# laser_show_peripheral.net
KiCad netlist of a schematic drawn in Altium Designer
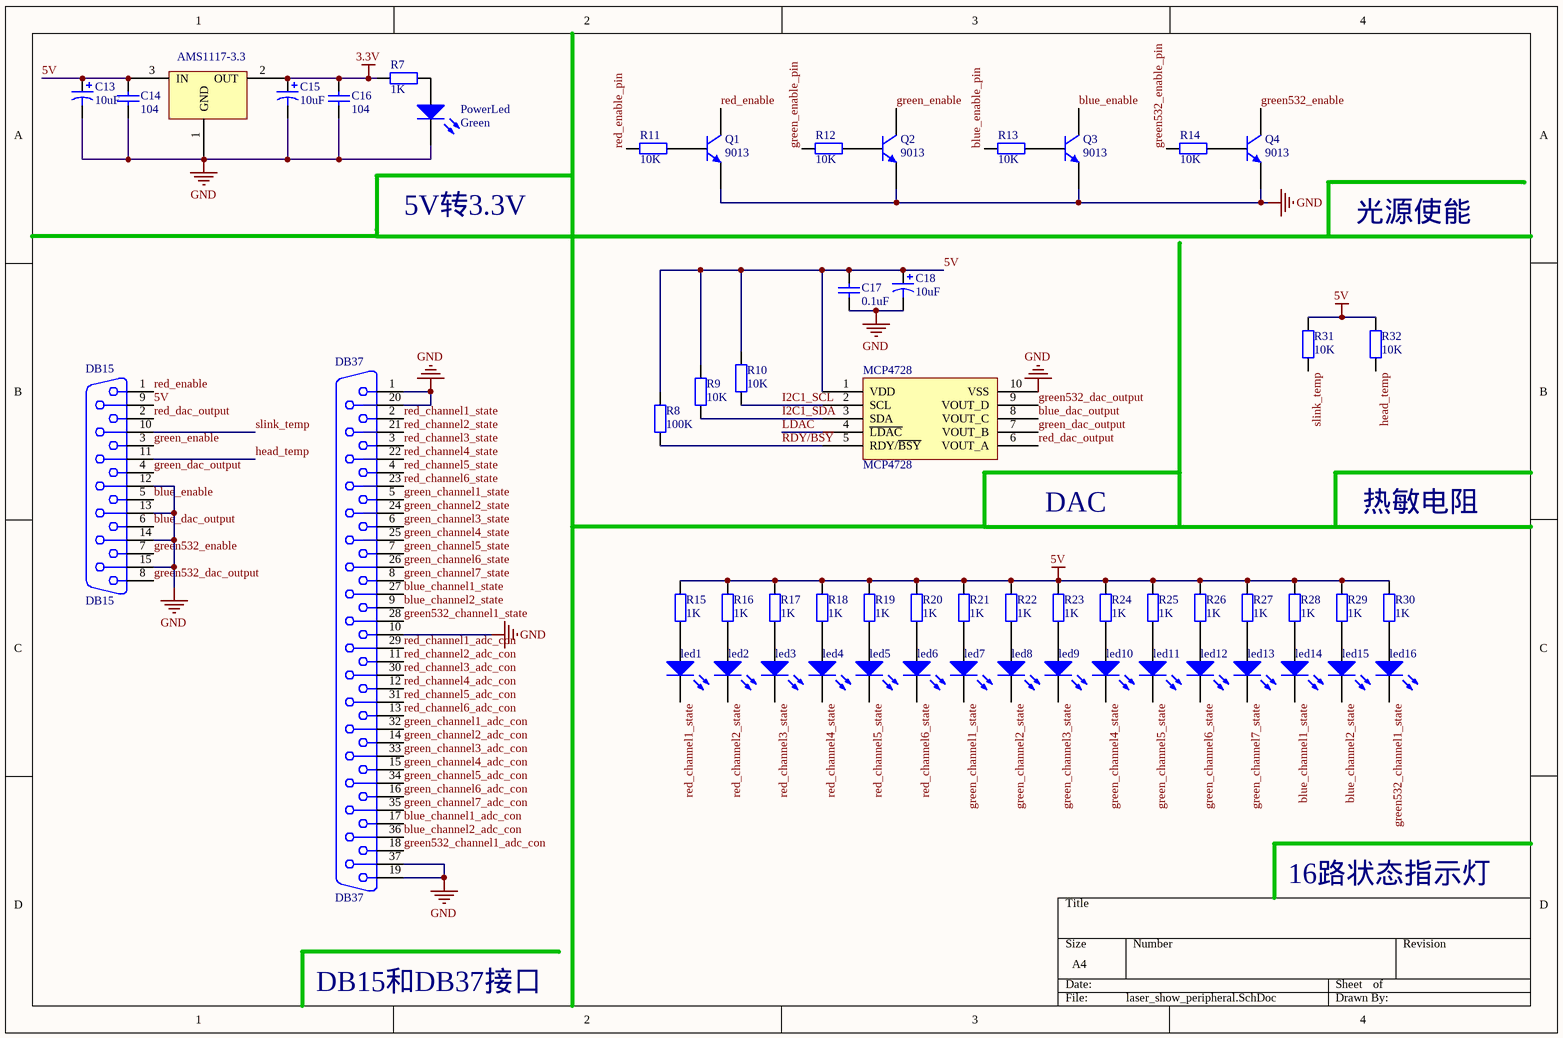
[diagram p0: laser_show_peripheral.SchDoc]

(export (version "E")
  (design (tool "Eeschema 10.0.6"))
  (components
    (comp (ref "AMS1117-3.3")
      (value "ASM1117")
      (footprint "ASM1117")
      (libsource (lib "RobotSCHLibrary") (part "ASM1117"))
    )
    (comp (ref "C13")
      (value "10uF")
      (footprint "0805CAP_POL")
      (description "Cap polar")
      (libsource (lib "RobotSCHLibrary") (part "CAP_Polar"))
    )
    (comp (ref "C14")
      (value "104")
      (footprint "0805C")
      (description "capacitance")
      (libsource (lib "RobotSCHLibrary") (part "CAP"))
    )
    (comp (ref "C15")
      (value "10uF")
      (footprint "0805CAP_POL")
      (description "Cap polar")
      (libsource (lib "RobotSCHLibrary") (part "CAP_Polar"))
    )
    (comp (ref "C16")
      (value "104")
      (footprint "0805C")
      (description "capacitance")
      (libsource (lib "RobotSCHLibrary") (part "CAP"))
    )
    (comp (ref "C17")
      (value "0.1uF")
      (footprint "0603C")
      (description "capacitance")
      (libsource (lib "RobotSCHLibrary") (part "CAP"))
    )
    (comp (ref "C18")
      (value "10uF")
      (footprint "0805CAP_POL")
      (description "Cap polar")
      (libsource (lib "RobotSCHLibrary") (part "CAP_Polar"))
    )
    (comp (ref "DB15") (value "DB15") (footprint "DB15/M") (libsource (lib "RobotSCHLibrary") (part "DB15")))
    (comp (ref "DB37") (value "DB37") (footprint "DB37/M") (libsource (lib "RobotSCHLibrary") (part "DB37")))
    (comp (ref "led1")
      (value "red")
      (footprint "0805-LED")
      (description "LED")
      (libsource (lib "RobotSCHLibrary") (part "LED"))
    )
    (comp (ref "led2")
      (value "red")
      (footprint "0805-LED")
      (description "LED")
      (libsource (lib "RobotSCHLibrary") (part "LED"))
    )
    (comp (ref "led3")
      (value "red")
      (footprint "0805-LED")
      (description "LED")
      (libsource (lib "RobotSCHLibrary") (part "LED"))
    )
    (comp (ref "led4")
      (value "red")
      (footprint "0805-LED")
      (description "LED")
      (libsource (lib "RobotSCHLibrary") (part "LED"))
    )
    (comp (ref "led5")
      (value "red")
      (footprint "0805-LED")
      (description "LED")
      (libsource (lib "RobotSCHLibrary") (part "LED"))
    )
    (comp (ref "led6")
      (value "red")
      (footprint "0805-LED")
      (description "LED")
      (libsource (lib "RobotSCHLibrary") (part "LED"))
    )
    (comp (ref "led7")
      (value "red")
      (footprint "0805-LED")
      (description "LED")
      (libsource (lib "RobotSCHLibrary") (part "LED"))
    )
    (comp (ref "led8")
      (value "red")
      (footprint "0805-LED")
      (description "LED")
      (libsource (lib "RobotSCHLibrary") (part "LED"))
    )
    (comp (ref "led9")
      (value "red")
      (footprint "0805-LED")
      (description "LED")
      (libsource (lib "RobotSCHLibrary") (part "LED"))
    )
    (comp (ref "led10")
      (value "red")
      (footprint "0805-LED")
      (description "LED")
      (libsource (lib "RobotSCHLibrary") (part "LED"))
    )
    (comp (ref "led11")
      (value "red")
      (footprint "0805-LED")
      (description "LED")
      (libsource (lib "RobotSCHLibrary") (part "LED"))
    )
    (comp (ref "led12")
      (value "red")
      (footprint "0805-LED")
      (description "LED")
      (libsource (lib "RobotSCHLibrary") (part "LED"))
    )
    (comp (ref "led13")
      (value "red")
      (footprint "0805-LED")
      (description "LED")
      (libsource (lib "RobotSCHLibrary") (part "LED"))
    )
    (comp (ref "led14")
      (value "red")
      (footprint "0805-LED")
      (description "LED")
      (libsource (lib "RobotSCHLibrary") (part "LED"))
    )
    (comp (ref "led15")
      (value "red")
      (footprint "0805-LED")
      (description "LED")
      (libsource (lib "RobotSCHLibrary") (part "LED"))
    )
    (comp (ref "led16")
      (value "red")
      (footprint "0805-LED")
      (description "LED")
      (libsource (lib "RobotSCHLibrary") (part "LED"))
    )
    (comp (ref "MCP4728")
      (value "MCP4728")
      (footprint "MSOP10")
      (libsource (lib "RobotSCHLibrary") (part "MCP4728"))
    )
    (comp (ref "PowerLed")
      (value "Green")
      (footprint "0805-LED")
      (description "LED")
      (libsource (lib "RobotSCHLibrary") (part "LED"))
    )
    (comp (ref "Q1")
      (value "9013")
      (footprint "SOT23_L")
      (description "NPN General Purpose Amplifier")
      (fields (field (name "PUBLISHER") "Altium Limited"))
      (libsource (lib "Miscellaneous Devices") (part "2N3904"))
    )
    (comp (ref "Q2")
      (value "9013")
      (footprint "SOT23_L")
      (description "NPN General Purpose Amplifier")
      (fields (field (name "PUBLISHER") "Altium Limited"))
      (libsource (lib "Miscellaneous Devices") (part "2N3904"))
    )
    (comp (ref "Q3")
      (value "9013")
      (footprint "SOT23_L")
      (description "NPN General Purpose Amplifier")
      (fields (field (name "PUBLISHER") "Altium Limited"))
      (libsource (lib "Miscellaneous Devices") (part "2N3904"))
    )
    (comp (ref "Q4")
      (value "9013")
      (footprint "SOT23_L")
      (description "NPN General Purpose Amplifier")
      (fields (field (name "PUBLISHER") "Altium Limited"))
      (libsource (lib "Miscellaneous Devices") (part "2N3904"))
    )
    (comp (ref "R7")
      (value "1K")
      (footprint "0805R")
      (description "resistor")
      (libsource (lib "") (part "RES_3"))
    )
    (comp (ref "R8")
      (value "100K")
      (footprint "0603R")
      (description "resistor")
      (libsource (lib "RobotSCHLibrary") (part "RES"))
    )
    (comp (ref "R9")
      (value "10K")
      (footprint "0603R")
      (description "resistor")
      (libsource (lib "RobotSCHLibrary") (part "RES"))
    )
    (comp (ref "R10")
      (value "10K")
      (footprint "0603R")
      (description "resistor")
      (libsource (lib "RobotSCHLibrary") (part "RES"))
    )
    (comp (ref "R11")
      (value "10K")
      (footprint "0805R")
      (description "resistor")
      (libsource (lib "") (part "RES_2"))
    )
    (comp (ref "R12")
      (value "10K")
      (footprint "0805R")
      (description "resistor")
      (libsource (lib "") (part "RES_1"))
    )
    (comp (ref "R13")
      (value "10K")
      (footprint "0805R")
      (description "resistor")
      (libsource (lib "") (part "RES_1"))
    )
    (comp (ref "R14")
      (value "10K")
      (footprint "0805R")
      (description "resistor")
      (libsource (lib "") (part "RES_1"))
    )
    (comp (ref "R15")
      (value "1K")
      (footprint "0805R")
      (description "resistor")
      (libsource (lib "RobotSCHLibrary") (part "RES"))
    )
    (comp (ref "R16")
      (value "1K")
      (footprint "0805R")
      (description "resistor")
      (libsource (lib "RobotSCHLibrary") (part "RES"))
    )
    (comp (ref "R17")
      (value "1K")
      (footprint "0805R")
      (description "resistor")
      (libsource (lib "RobotSCHLibrary") (part "RES"))
    )
    (comp (ref "R18")
      (value "1K")
      (footprint "0805R")
      (description "resistor")
      (libsource (lib "RobotSCHLibrary") (part "RES"))
    )
    (comp (ref "R19")
      (value "1K")
      (footprint "0805R")
      (description "resistor")
      (libsource (lib "RobotSCHLibrary") (part "RES"))
    )
    (comp (ref "R20")
      (value "1K")
      (footprint "0805R")
      (description "resistor")
      (libsource (lib "RobotSCHLibrary") (part "RES"))
    )
    (comp (ref "R21")
      (value "1K")
      (footprint "0805R")
      (description "resistor")
      (libsource (lib "RobotSCHLibrary") (part "RES"))
    )
    (comp (ref "R22")
      (value "1K")
      (footprint "0805R")
      (description "resistor")
      (libsource (lib "RobotSCHLibrary") (part "RES"))
    )
    (comp (ref "R23")
      (value "1K")
      (footprint "0805R")
      (description "resistor")
      (libsource (lib "RobotSCHLibrary") (part "RES"))
    )
    (comp (ref "R24")
      (value "1K")
      (footprint "0805R")
      (description "resistor")
      (libsource (lib "RobotSCHLibrary") (part "RES"))
    )
    (comp (ref "R25")
      (value "1K")
      (footprint "0805R")
      (description "resistor")
      (libsource (lib "RobotSCHLibrary") (part "RES"))
    )
    (comp (ref "R26")
      (value "1K")
      (footprint "0805R")
      (description "resistor")
      (libsource (lib "RobotSCHLibrary") (part "RES"))
    )
    (comp (ref "R27")
      (value "1K")
      (footprint "0805R")
      (description "resistor")
      (libsource (lib "RobotSCHLibrary") (part "RES"))
    )
    (comp (ref "R28")
      (value "1K")
      (footprint "0805R")
      (description "resistor")
      (libsource (lib "RobotSCHLibrary") (part "RES"))
    )
    (comp (ref "R29")
      (value "1K")
      (footprint "0805R")
      (description "resistor")
      (libsource (lib "RobotSCHLibrary") (part "RES"))
    )
    (comp (ref "R30")
      (value "1K")
      (footprint "0805R")
      (description "resistor")
      (libsource (lib "RobotSCHLibrary") (part "RES"))
    )
    (comp (ref "R31")
      (value "10K")
      (footprint "0805R")
      (description "resistor")
      (libsource (lib "RobotSCHLibrary") (part "RES"))
    )
    (comp (ref "R32")
      (value "10K")
      (footprint "0805R")
      (description "resistor")
      (libsource (lib "RobotSCHLibrary") (part "RES"))
    )
  )
  (nets
    (net (code "1") (name "/I2C1_SCL") (class "Default")
      (node (ref "MCP4728") (pin "2") (pinfunction "SCL_2") (pintype "passive"))
      (node (ref "R10") (pin "1") (pinfunction "1_1") (pintype "passive"))
    )
    (net (code "2") (name "/I2C1_SDA") (class "Default")
      (node (ref "MCP4728") (pin "3") (pinfunction "SDA_3") (pintype "passive"))
      (node (ref "R9") (pin "1") (pinfunction "1_1") (pintype "passive"))
    )
    (net (code "3") (name "/RDY{slash}~{BSY}") (class "Default")
      (node (ref "MCP4728") (pin "5") (pinfunction "RDY/~{BSY}_5") (pintype "passive"))
      (node (ref "R8") (pin "1") (pinfunction "1_1") (pintype "passive"))
    )
    (net (code "4") (name "/blue_channel1_adc_con") (class "Default")
      (node (ref "DB37") (pin "17") (pinfunction "17_17") (pintype "passive"))
    )
    (net (code "5") (name "/blue_channel1_state") (class "Default")
      (node (ref "DB37") (pin "27") (pinfunction "27_27") (pintype "passive"))
      (node (ref "led14") (pin "2") (pinfunction "K_2") (pintype "passive"))
    )
    (net (code "6") (name "/blue_channel2_adc_con") (class "Default")
      (node (ref "DB37") (pin "36") (pinfunction "36_36") (pintype "passive"))
    )
    (net (code "7") (name "/blue_channel2_state") (class "Default")
      (node (ref "DB37") (pin "9") (pinfunction "9_9") (pintype "passive"))
      (node (ref "led15") (pin "2") (pinfunction "K_2") (pintype "passive"))
    )
    (net (code "8") (name "/blue_dac_output") (class "Default")
      (node (ref "DB15") (pin "6") (pinfunction "6_6") (pintype "passive"))
      (node (ref "MCP4728") (pin "8") (pinfunction "VOUT_C_8") (pintype "passive"))
    )
    (net (code "9") (name "/blue_enable") (class "Default")
      (node (ref "DB15") (pin "5") (pinfunction "5_5") (pintype "passive"))
      (node (ref "Q3") (pin "3") (pinfunction "C_3") (pintype "passive"))
    )
    (net (code "10") (name "/blue_enable_pin") (class "Default")
      (node (ref "R13") (pin "2") (pinfunction "2_2") (pintype "passive"))
    )
    (net (code "11") (name "/green532_channel1_adc_con") (class "Default")
      (node (ref "DB37") (pin "18") (pinfunction "18_18") (pintype "passive"))
    )
    (net (code "12") (name "/green532_channel1_state") (class "Default")
      (node (ref "DB37") (pin "28") (pinfunction "28_28") (pintype "passive"))
      (node (ref "led16") (pin "2") (pinfunction "K_2") (pintype "passive"))
    )
    (net (code "13") (name "/green532_dac_output") (class "Default")
      (node (ref "DB15") (pin "8") (pinfunction "8_8") (pintype "passive"))
      (node (ref "MCP4728") (pin "9") (pinfunction "VOUT_D_9") (pintype "passive"))
    )
    (net (code "14") (name "/green532_enable") (class "Default")
      (node (ref "DB15") (pin "7") (pinfunction "7_7") (pintype "passive"))
      (node (ref "Q4") (pin "3") (pinfunction "C_3") (pintype "passive"))
    )
    (net (code "15") (name "/green532_enable_pin") (class "Default")
      (node (ref "R14") (pin "2") (pinfunction "2_2") (pintype "passive"))
    )
    (net (code "16") (name "/green_channel1_adc_con") (class "Default")
      (node (ref "DB37") (pin "32") (pinfunction "32_32") (pintype "passive"))
    )
    (net (code "17") (name "/green_channel1_state") (class "Default")
      (node (ref "DB37") (pin "5") (pinfunction "5_5") (pintype "passive"))
      (node (ref "led7") (pin "2") (pinfunction "K_2") (pintype "passive"))
    )
    (net (code "18") (name "/green_channel2_adc_con") (class "Default")
      (node (ref "DB37") (pin "14") (pinfunction "14_14") (pintype "passive"))
    )
    (net (code "19") (name "/green_channel2_state") (class "Default")
      (node (ref "DB37") (pin "24") (pinfunction "24_24") (pintype "passive"))
      (node (ref "led8") (pin "2") (pinfunction "K_2") (pintype "passive"))
    )
    (net (code "20") (name "/green_channel3_adc_con") (class "Default")
      (node (ref "DB37") (pin "33") (pinfunction "33_33") (pintype "passive"))
    )
    (net (code "21") (name "/green_channel3_state") (class "Default")
      (node (ref "DB37") (pin "6") (pinfunction "6_6") (pintype "passive"))
      (node (ref "led9") (pin "2") (pinfunction "K_2") (pintype "passive"))
    )
    (net (code "22") (name "/green_channel4_adc_con") (class "Default")
      (node (ref "DB37") (pin "15") (pinfunction "15_15") (pintype "passive"))
    )
    (net (code "23") (name "/green_channel4_state") (class "Default")
      (node (ref "DB37") (pin "25") (pinfunction "25_25") (pintype "passive"))
      (node (ref "led10") (pin "2") (pinfunction "K_2") (pintype "passive"))
    )
    (net (code "24") (name "/green_channel5_adc_con") (class "Default")
      (node (ref "DB37") (pin "34") (pinfunction "34_34") (pintype "passive"))
    )
    (net (code "25") (name "/green_channel5_state") (class "Default")
      (node (ref "DB37") (pin "7") (pinfunction "7_7") (pintype "passive"))
      (node (ref "led11") (pin "2") (pinfunction "K_2") (pintype "passive"))
    )
    (net (code "26") (name "/green_channel6_adc_con") (class "Default")
      (node (ref "DB37") (pin "16") (pinfunction "16_16") (pintype "passive"))
    )
    (net (code "27") (name "/green_channel6_state") (class "Default")
      (node (ref "DB37") (pin "26") (pinfunction "26_26") (pintype "passive"))
      (node (ref "led12") (pin "2") (pinfunction "K_2") (pintype "passive"))
    )
    (net (code "28") (name "/green_channel7_adc_con") (class "Default")
      (node (ref "DB37") (pin "35") (pinfunction "35_35") (pintype "passive"))
    )
    (net (code "29") (name "/green_channel7_state") (class "Default")
      (node (ref "DB37") (pin "8") (pinfunction "8_8") (pintype "passive"))
      (node (ref "led13") (pin "2") (pinfunction "K_2") (pintype "passive"))
    )
    (net (code "30") (name "/green_dac_output") (class "Default")
      (node (ref "DB15") (pin "4") (pinfunction "4_4") (pintype "passive"))
      (node (ref "MCP4728") (pin "7") (pinfunction "VOUT_B_7") (pintype "passive"))
    )
    (net (code "31") (name "/green_enable") (class "Default")
      (node (ref "DB15") (pin "3") (pinfunction "3_3") (pintype "passive"))
      (node (ref "Q2") (pin "3") (pinfunction "C_3") (pintype "passive"))
    )
    (net (code "32") (name "/green_enable_pin") (class "Default")
      (node (ref "R12") (pin "2") (pinfunction "2_2") (pintype "passive"))
    )
    (net (code "33") (name "/head_temp") (class "Default")
      (node (ref "DB15") (pin "11") (pinfunction "11_11") (pintype "passive"))
      (node (ref "R32") (pin "1") (pinfunction "1_1") (pintype "passive"))
    )
    (net (code "34") (name "/red_channel1_adc_con") (class "Default")
      (node (ref "DB37") (pin "29") (pinfunction "29_29") (pintype "passive"))
    )
    (net (code "35") (name "/red_channel1_state") (class "Default")
      (node (ref "DB37") (pin "2") (pinfunction "2_2") (pintype "passive"))
      (node (ref "led1") (pin "2") (pinfunction "K_2") (pintype "passive"))
    )
    (net (code "36") (name "/red_channel2_adc_con") (class "Default")
      (node (ref "DB37") (pin "11") (pinfunction "11_11") (pintype "passive"))
    )
    (net (code "37") (name "/red_channel2_state") (class "Default")
      (node (ref "DB37") (pin "21") (pinfunction "21_21") (pintype "passive"))
      (node (ref "led2") (pin "2") (pinfunction "K_2") (pintype "passive"))
    )
    (net (code "38") (name "/red_channel3_adc_con") (class "Default")
      (node (ref "DB37") (pin "30") (pinfunction "30_30") (pintype "passive"))
    )
    (net (code "39") (name "/red_channel3_state") (class "Default")
      (node (ref "DB37") (pin "3") (pinfunction "3_3") (pintype "passive"))
      (node (ref "led3") (pin "2") (pinfunction "K_2") (pintype "passive"))
    )
    (net (code "40") (name "/red_channel4_adc_con") (class "Default")
      (node (ref "DB37") (pin "12") (pinfunction "12_12") (pintype "passive"))
    )
    (net (code "41") (name "/red_channel4_state") (class "Default")
      (node (ref "DB37") (pin "22") (pinfunction "22_22") (pintype "passive"))
      (node (ref "led4") (pin "2") (pinfunction "K_2") (pintype "passive"))
    )
    (net (code "42") (name "/red_channel5_adc_con") (class "Default")
      (node (ref "DB37") (pin "31") (pinfunction "31_31") (pintype "passive"))
    )
    (net (code "43") (name "/red_channel5_state") (class "Default")
      (node (ref "DB37") (pin "4") (pinfunction "4_4") (pintype "passive"))
      (node (ref "led5") (pin "2") (pinfunction "K_2") (pintype "passive"))
    )
    (net (code "44") (name "/red_channel6_adc_con") (class "Default")
      (node (ref "DB37") (pin "13") (pinfunction "13_13") (pintype "passive"))
    )
    (net (code "45") (name "/red_channel6_state") (class "Default")
      (node (ref "DB37") (pin "23") (pinfunction "23_23") (pintype "passive"))
      (node (ref "led6") (pin "2") (pinfunction "K_2") (pintype "passive"))
    )
    (net (code "46") (name "/red_dac_output") (class "Default")
      (node (ref "DB15") (pin "2") (pinfunction "2_2") (pintype "passive"))
      (node (ref "MCP4728") (pin "6") (pinfunction "VOUT_A_6") (pintype "passive"))
    )
    (net (code "47") (name "/red_enable") (class "Default")
      (node (ref "DB15") (pin "1") (pinfunction "1_1") (pintype "passive"))
      (node (ref "Q1") (pin "3") (pinfunction "C_3") (pintype "passive"))
    )
    (net (code "48") (name "/red_enable_pin") (class "Default")
      (node (ref "R11") (pin "2") (pinfunction "2_2") (pintype "passive"))
    )
    (net (code "49") (name "/slink_temp") (class "Default")
      (node (ref "DB15") (pin "10") (pinfunction "10_10") (pintype "passive"))
      (node (ref "R31") (pin "1") (pinfunction "1_1") (pintype "passive"))
    )
    (net (code "50") (name "/~{LDA}C") (class "Default")
      (node (ref "MCP4728") (pin "4") (pinfunction "~{LDAC}_4") (pintype "passive"))
    )
    (net (code "51") (name "3.3V") (class "Default")
      (node (ref "AMS1117-3.3") (pin "2") (pinfunction "OUT_2") (pintype "passive"))
      (node (ref "C15") (pin "1") (pinfunction "1_1") (pintype "passive"))
      (node (ref "C16") (pin "2") (pinfunction "2_2") (pintype "passive"))
      (node (ref "R7") (pin "1") (pinfunction "1_1") (pintype "passive"))
    )
    (net (code "52") (name "5V") (class "Default")
      (node (ref "AMS1117-3.3") (pin "3") (pinfunction "IN_3") (pintype "passive"))
      (node (ref "C13") (pin "1") (pinfunction "1_1") (pintype "passive"))
      (node (ref "C14") (pin "2") (pinfunction "2_2") (pintype "passive"))
      (node (ref "C17") (pin "2") (pinfunction "2_2") (pintype "passive"))
      (node (ref "C18") (pin "1") (pinfunction "1_1") (pintype "passive"))
      (node (ref "DB15") (pin "9") (pinfunction "9_9") (pintype "passive"))
      (node (ref "MCP4728") (pin "1") (pinfunction "VDD_1") (pintype "passive"))
      (node (ref "R10") (pin "2") (pinfunction "2_2") (pintype "passive"))
      (node (ref "R15") (pin "2") (pinfunction "2_2") (pintype "passive"))
      (node (ref "R16") (pin "2") (pinfunction "2_2") (pintype "passive"))
      (node (ref "R17") (pin "2") (pinfunction "2_2") (pintype "passive"))
      (node (ref "R18") (pin "2") (pinfunction "2_2") (pintype "passive"))
      (node (ref "R19") (pin "2") (pinfunction "2_2") (pintype "passive"))
      (node (ref "R20") (pin "2") (pinfunction "2_2") (pintype "passive"))
      (node (ref "R21") (pin "2") (pinfunction "2_2") (pintype "passive"))
      (node (ref "R22") (pin "2") (pinfunction "2_2") (pintype "passive"))
      (node (ref "R23") (pin "2") (pinfunction "2_2") (pintype "passive"))
      (node (ref "R24") (pin "2") (pinfunction "2_2") (pintype "passive"))
      (node (ref "R25") (pin "2") (pinfunction "2_2") (pintype "passive"))
      (node (ref "R26") (pin "2") (pinfunction "2_2") (pintype "passive"))
      (node (ref "R27") (pin "2") (pinfunction "2_2") (pintype "passive"))
      (node (ref "R28") (pin "2") (pinfunction "2_2") (pintype "passive"))
      (node (ref "R29") (pin "2") (pinfunction "2_2") (pintype "passive"))
      (node (ref "R30") (pin "2") (pinfunction "2_2") (pintype "passive"))
      (node (ref "R31") (pin "2") (pinfunction "2_2") (pintype "passive"))
      (node (ref "R32") (pin "2") (pinfunction "2_2") (pintype "passive"))
      (node (ref "R8") (pin "2") (pinfunction "2_2") (pintype "passive"))
      (node (ref "R9") (pin "2") (pinfunction "2_2") (pintype "passive"))
    )
    (net (code "53") (name "GND") (class "Default")
      (node (ref "AMS1117-3.3") (pin "1") (pinfunction "GND_1") (pintype "passive"))
      (node (ref "C13") (pin "2") (pinfunction "2_2") (pintype "passive"))
      (node (ref "C14") (pin "1") (pinfunction "1_1") (pintype "passive"))
      (node (ref "C15") (pin "2") (pinfunction "2_2") (pintype "passive"))
      (node (ref "C16") (pin "1") (pinfunction "1_1") (pintype "passive"))
      (node (ref "C17") (pin "1") (pinfunction "1_1") (pintype "passive"))
      (node (ref "C18") (pin "2") (pinfunction "2_2") (pintype "passive"))
      (node (ref "DB15") (pin "12") (pinfunction "12_12") (pintype "passive"))
      (node (ref "DB15") (pin "13") (pinfunction "13_13") (pintype "passive"))
      (node (ref "DB15") (pin "14") (pinfunction "14_14") (pintype "passive"))
      (node (ref "DB15") (pin "15") (pinfunction "15_15") (pintype "passive"))
      (node (ref "DB37") (pin "1") (pinfunction "1_1") (pintype "passive"))
      (node (ref "DB37") (pin "10") (pinfunction "10_10") (pintype "passive"))
      (node (ref "DB37") (pin "19") (pinfunction "19_19") (pintype "passive"))
      (node (ref "DB37") (pin "20") (pinfunction "20_20") (pintype "passive"))
      (node (ref "DB37") (pin "37") (pinfunction "37_37") (pintype "passive"))
      (node (ref "MCP4728") (pin "10") (pinfunction "VSS_10") (pintype "passive"))
      (node (ref "PowerLed") (pin "2") (pinfunction "K_2") (pintype "passive"))
      (node (ref "Q1") (pin "1") (pinfunction "E_1") (pintype "passive"))
      (node (ref "Q2") (pin "1") (pinfunction "E_1") (pintype "passive"))
      (node (ref "Q3") (pin "1") (pinfunction "E_1") (pintype "passive"))
      (node (ref "Q4") (pin "1") (pinfunction "E_1") (pintype "passive"))
    )
    (net (code "54") (name "Net-(PowerLed-A)") (class "Default")
      (node (ref "PowerLed") (pin "1") (pinfunction "A_1") (pintype "passive"))
      (node (ref "R7") (pin "2") (pinfunction "2_2") (pintype "passive"))
    )
    (net (code "55") (name "Net-(Q1-B)") (class "Default")
      (node (ref "Q1") (pin "2") (pinfunction "B_2") (pintype "passive"))
      (node (ref "R11") (pin "1") (pinfunction "1_1") (pintype "passive"))
    )
    (net (code "56") (name "Net-(Q2-B)") (class "Default")
      (node (ref "Q2") (pin "2") (pinfunction "B_2") (pintype "passive"))
      (node (ref "R12") (pin "1") (pinfunction "1_1") (pintype "passive"))
    )
    (net (code "57") (name "Net-(Q3-B)") (class "Default")
      (node (ref "Q3") (pin "2") (pinfunction "B_2") (pintype "passive"))
      (node (ref "R13") (pin "1") (pinfunction "1_1") (pintype "passive"))
    )
    (net (code "58") (name "Net-(Q4-B)") (class "Default")
      (node (ref "Q4") (pin "2") (pinfunction "B_2") (pintype "passive"))
      (node (ref "R14") (pin "1") (pinfunction "1_1") (pintype "passive"))
    )
    (net (code "59") (name "Net-(led1-A)") (class "Default")
      (node (ref "R15") (pin "1") (pinfunction "1_1") (pintype "passive"))
      (node (ref "led1") (pin "1") (pinfunction "A_1") (pintype "passive"))
    )
    (net (code "60") (name "Net-(led2-A)") (class "Default")
      (node (ref "R16") (pin "1") (pinfunction "1_1") (pintype "passive"))
      (node (ref "led2") (pin "1") (pinfunction "A_1") (pintype "passive"))
    )
    (net (code "61") (name "Net-(led3-A)") (class "Default")
      (node (ref "R17") (pin "1") (pinfunction "1_1") (pintype "passive"))
      (node (ref "led3") (pin "1") (pinfunction "A_1") (pintype "passive"))
    )
    (net (code "62") (name "Net-(led4-A)") (class "Default")
      (node (ref "R18") (pin "1") (pinfunction "1_1") (pintype "passive"))
      (node (ref "led4") (pin "1") (pinfunction "A_1") (pintype "passive"))
    )
    (net (code "63") (name "Net-(led5-A)") (class "Default")
      (node (ref "R19") (pin "1") (pinfunction "1_1") (pintype "passive"))
      (node (ref "led5") (pin "1") (pinfunction "A_1") (pintype "passive"))
    )
    (net (code "64") (name "Net-(led6-A)") (class "Default")
      (node (ref "R20") (pin "1") (pinfunction "1_1") (pintype "passive"))
      (node (ref "led6") (pin "1") (pinfunction "A_1") (pintype "passive"))
    )
    (net (code "65") (name "Net-(led7-A)") (class "Default")
      (node (ref "R21") (pin "1") (pinfunction "1_1") (pintype "passive"))
      (node (ref "led7") (pin "1") (pinfunction "A_1") (pintype "passive"))
    )
    (net (code "66") (name "Net-(led8-A)") (class "Default")
      (node (ref "R22") (pin "1") (pinfunction "1_1") (pintype "passive"))
      (node (ref "led8") (pin "1") (pinfunction "A_1") (pintype "passive"))
    )
    (net (code "67") (name "Net-(led9-A)") (class "Default")
      (node (ref "R23") (pin "1") (pinfunction "1_1") (pintype "passive"))
      (node (ref "led9") (pin "1") (pinfunction "A_1") (pintype "passive"))
    )
    (net (code "68") (name "Net-(led10-A)") (class "Default")
      (node (ref "R24") (pin "1") (pinfunction "1_1") (pintype "passive"))
      (node (ref "led10") (pin "1") (pinfunction "A_1") (pintype "passive"))
    )
    (net (code "69") (name "Net-(led11-A)") (class "Default")
      (node (ref "R25") (pin "1") (pinfunction "1_1") (pintype "passive"))
      (node (ref "led11") (pin "1") (pinfunction "A_1") (pintype "passive"))
    )
    (net (code "70") (name "Net-(led12-A)") (class "Default")
      (node (ref "R26") (pin "1") (pinfunction "1_1") (pintype "passive"))
      (node (ref "led12") (pin "1") (pinfunction "A_1") (pintype "passive"))
    )
    (net (code "71") (name "Net-(led13-A)") (class "Default")
      (node (ref "R27") (pin "1") (pinfunction "1_1") (pintype "passive"))
      (node (ref "led13") (pin "1") (pinfunction "A_1") (pintype "passive"))
    )
    (net (code "72") (name "Net-(led14-A)") (class "Default")
      (node (ref "R28") (pin "1") (pinfunction "1_1") (pintype "passive"))
      (node (ref "led14") (pin "1") (pinfunction "A_1") (pintype "passive"))
    )
    (net (code "73") (name "Net-(led15-A)") (class "Default")
      (node (ref "R29") (pin "1") (pinfunction "1_1") (pintype "passive"))
      (node (ref "led15") (pin "1") (pinfunction "A_1") (pintype "passive"))
    )
    (net (code "74") (name "Net-(led16-A)") (class "Default")
      (node (ref "R30") (pin "1") (pinfunction "1_1") (pintype "passive"))
      (node (ref "led16") (pin "1") (pinfunction "A_1") (pintype "passive"))
    )
  )
)
